# MCU.net
KiCad netlist of a schematic drawn in Altium Designer
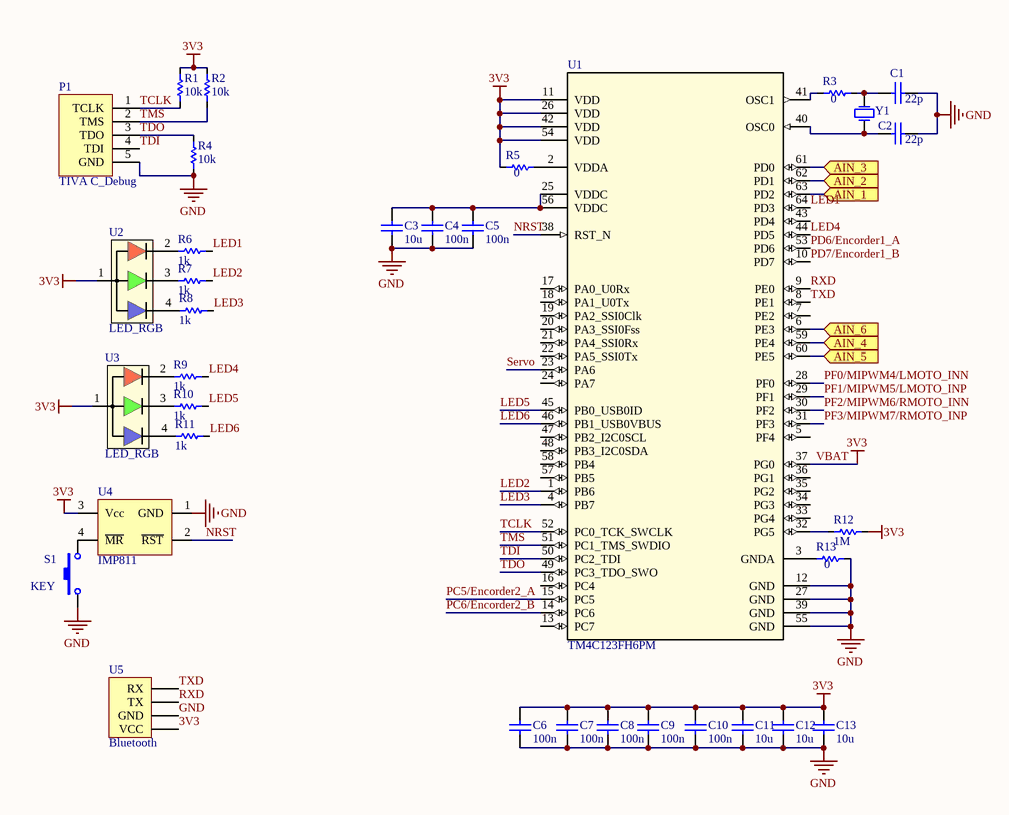
[diagram p0: MCU.SchDoc]

(export (version "E")
  (design (tool "Eeschema 10.0.6"))
  (components
    (comp (ref "C1")
      (value "22p")
      (footprint "0603C")
      (description "Capacitor")
      (fields (field (name "Comment") "1uF/0603/50V") (field (name "PUBLISHER") "Altium Limited"))
      (libsource (lib "OurSuperMiniCar") (part "Cap"))
    )
    (comp (ref "C2")
      (value "22p")
      (footprint "0603C")
      (description "Capacitor")
      (fields (field (name "Comment") "1uF/0603/50V") (field (name "PUBLISHER") "Altium Limited"))
      (libsource (lib "OurSuperMiniCar") (part "Cap"))
    )
    (comp (ref "C3")
      (value "10u")
      (footprint "0603C")
      (description "Capacitor")
      (fields (field (name "Comment") "1uF/0603/50V") (field (name "PUBLISHER") "Altium Limited"))
      (libsource (lib "OurSuperMiniCar") (part "Cap"))
    )
    (comp (ref "C4")
      (value "100n")
      (footprint "0603C")
      (description "Capacitor")
      (fields (field (name "Comment") "1uF/0603/50V") (field (name "PUBLISHER") "Altium Limited"))
      (libsource (lib "OurSuperMiniCar") (part "Cap"))
    )
    (comp (ref "C5")
      (value "100n")
      (footprint "0603C")
      (description "Capacitor")
      (fields (field (name "Comment") "1uF/0603/50V") (field (name "PUBLISHER") "Altium Limited"))
      (libsource (lib "OurSuperMiniCar") (part "Cap"))
    )
    (comp (ref "C6")
      (value "100n")
      (footprint "0603C")
      (description "Capacitor")
      (fields (field (name "Comment") "1uF/0603/50V") (field (name "PUBLISHER") "Altium Limited"))
      (libsource (lib "OurSuperMiniCar") (part "Cap"))
    )
    (comp (ref "C7")
      (value "100n")
      (footprint "0603C")
      (description "Capacitor")
      (fields (field (name "Comment") "1uF/0603/50V") (field (name "PUBLISHER") "Altium Limited"))
      (libsource (lib "OurSuperMiniCar") (part "Cap"))
    )
    (comp (ref "C8")
      (value "100n")
      (footprint "0603C")
      (description "Capacitor")
      (fields (field (name "Comment") "1uF/0603/50V") (field (name "PUBLISHER") "Altium Limited"))
      (libsource (lib "OurSuperMiniCar") (part "Cap"))
    )
    (comp (ref "C9")
      (value "100n")
      (footprint "0603C")
      (description "Capacitor")
      (fields (field (name "Comment") "1uF/0603/50V") (field (name "PUBLISHER") "Altium Limited"))
      (libsource (lib "OurSuperMiniCar") (part "Cap"))
    )
    (comp (ref "C10")
      (value "100n")
      (footprint "0603C")
      (description "Capacitor")
      (fields (field (name "Comment") "1uF/0603/50V") (field (name "PUBLISHER") "Altium Limited"))
      (libsource (lib "OurSuperMiniCar") (part "Cap"))
    )
    (comp (ref "C11")
      (value "10u")
      (footprint "0603C")
      (description "Capacitor")
      (fields (field (name "Comment") "1uF/0603/50V") (field (name "PUBLISHER") "Altium Limited"))
      (libsource (lib "OurSuperMiniCar") (part "Cap"))
    )
    (comp (ref "C12")
      (value "10u")
      (footprint "0603C")
      (description "Capacitor")
      (fields (field (name "Comment") "1uF/0603/50V") (field (name "PUBLISHER") "Altium Limited"))
      (libsource (lib "OurSuperMiniCar") (part "Cap"))
    )
    (comp (ref "C13")
      (value "10u")
      (footprint "0603C")
      (description "Capacitor")
      (fields (field (name "Comment") "1uF/0603/50V") (field (name "PUBLISHER") "Altium Limited"))
      (libsource (lib "OurSuperMiniCar") (part "Cap"))
    )
    (comp (ref "P1")
      (value "TIVA C_Debug")
      (footprint "SMT_HEADER5")
      (libsource (lib "OurSuperMiniCar") (part "TIVA C_Debug"))
    )
    (comp (ref "R1")
      (value "10k")
      (footprint "0603R")
      (description "Resistor")
      (fields (field (name "Comment") "1K/5%") (field (name "PUBLISHER") "Altium Limited"))
      (libsource (lib "OurSuperMiniCar") (part "Res1"))
    )
    (comp (ref "R2")
      (value "10k")
      (footprint "0603R")
      (description "Resistor")
      (fields (field (name "Comment") "1K/5%") (field (name "PUBLISHER") "Altium Limited"))
      (libsource (lib "OurSuperMiniCar") (part "Res1"))
    )
    (comp (ref "R3")
      (value "0")
      (footprint "0603R")
      (description "Resistor")
      (fields (field (name "Comment") "1K/5%") (field (name "PUBLISHER") "Altium Limited"))
      (libsource (lib "OurSuperMiniCar") (part "Res1"))
    )
    (comp (ref "R4")
      (value "10k")
      (footprint "0603R")
      (description "Resistor")
      (fields (field (name "Comment") "1K/5%") (field (name "PUBLISHER") "Altium Limited"))
      (libsource (lib "OurSuperMiniCar") (part "Res1"))
    )
    (comp (ref "R5")
      (value "0")
      (footprint "0603R")
      (description "Resistor")
      (fields (field (name "Comment") "1K/5%") (field (name "PUBLISHER") "Altium Limited"))
      (libsource (lib "OurSuperMiniCar") (part "Res1"))
    )
    (comp (ref "R6")
      (value "1k")
      (footprint "0402")
      (description "Resistor")
      (fields (field (name "Comment") "1K/5%") (field (name "PUBLISHER") "Altium Limited"))
      (libsource (lib "OurSuperMiniCar") (part "Res1"))
    )
    (comp (ref "R7")
      (value "1k")
      (footprint "0402")
      (description "Resistor")
      (fields (field (name "Comment") "1K/5%") (field (name "PUBLISHER") "Altium Limited"))
      (libsource (lib "OurSuperMiniCar") (part "Res1"))
    )
    (comp (ref "R8")
      (value "1k")
      (footprint "0402")
      (description "Resistor")
      (fields (field (name "Comment") "1K/5%") (field (name "PUBLISHER") "Altium Limited"))
      (libsource (lib "OurSuperMiniCar") (part "Res1"))
    )
    (comp (ref "R9")
      (value "1k")
      (footprint "0402")
      (description "Resistor")
      (fields (field (name "Comment") "1K/5%") (field (name "PUBLISHER") "Altium Limited"))
      (libsource (lib "OurSuperMiniCar") (part "Res1"))
    )
    (comp (ref "R10")
      (value "1k")
      (footprint "0402")
      (description "Resistor")
      (fields (field (name "Comment") "1K/5%") (field (name "PUBLISHER") "Altium Limited"))
      (libsource (lib "OurSuperMiniCar") (part "Res1"))
    )
    (comp (ref "R11")
      (value "1k")
      (footprint "0402")
      (description "Resistor")
      (fields (field (name "Comment") "1K/5%") (field (name "PUBLISHER") "Altium Limited"))
      (libsource (lib "OurSuperMiniCar") (part "Res1"))
    )
    (comp (ref "R12")
      (value "1M")
      (footprint "0603R")
      (description "Resistor")
      (fields (field (name "Comment") "1K/5%") (field (name "PUBLISHER") "Altium Limited"))
      (libsource (lib "OurSuperMiniCar") (part "Res1"))
    )
    (comp (ref "R13")
      (value "0")
      (footprint "0603R")
      (description "Resistor")
      (fields (field (name "Comment") "1K/5%") (field (name "PUBLISHER") "Altium Limited"))
      (libsource (lib "OurSuperMiniCar") (part "Res1"))
    )
    (comp (ref "S1")
      (value "KEY")
      (footprint "SW-3x6mm-SMT")
      (description "Button")
      (fields (field (name "PUBLISHER") "Altium Limited"))
      (libsource (lib "OurSuperMiniCar") (part "PushButton_2p"))
    )
    (comp (ref "U1")
      (value "TM4C123FH6PM")
      (footprint "LQFP_64")
      (libsource (lib "OurSuperMiniCar") (part "TM4C123FH6PM"))
    )
    (comp (ref "U2")
      (value "LED_RGB")
      (footprint "0603 RGB")
      (libsource (lib "OurSuperMiniCar") (part "LED_RGB"))
    )
    (comp (ref "U3")
      (value "LED_RGB")
      (footprint "0603 RGB")
      (libsource (lib "OurSuperMiniCar") (part "LED_RGB"))
    )
    (comp (ref "U4")
      (value "IMP811")
      (footprint "SOT143")
      (description "复位芯片")
      (libsource (lib "OurSuperMiniCar") (part "IMP811"))
    )
    (comp (ref "U5")
      (value "Bluetooth")
      (footprint "SMT_Female HEADER4")
      (description "Bluetooth Module")
      (libsource (lib "OurSuperMiniCar") (part "Bluetooth"))
    )
    (comp (ref "Y1")
      (value "XTAL")
      (footprint "NX5032GA")
      (description "Crystal Oscillator")
      (fields (field (name "PUBLISHER") "Altium Limited"))
      (libsource (lib "OurSuperMiniCar") (part "XTAL"))
    )
  )
  (nets
    (net (code "1") (name "/AIN_1") (class "Default")
      (node (ref "U1") (pin "63") (pinfunction "PD2_63") (pintype "bidirectional"))
    )
    (net (code "2") (name "/AIN_2") (class "Default")
      (node (ref "U1") (pin "62") (pinfunction "PD1_62") (pintype "bidirectional"))
    )
    (net (code "3") (name "/AIN_3") (class "Default")
      (node (ref "U1") (pin "61") (pinfunction "PD0_61") (pintype "bidirectional"))
    )
    (net (code "4") (name "/AIN_4") (class "Default")
      (node (ref "U1") (pin "59") (pinfunction "PE4_59") (pintype "bidirectional"))
    )
    (net (code "5") (name "/AIN_5") (class "Default")
      (node (ref "U1") (pin "60") (pinfunction "PE5_60") (pintype "bidirectional"))
    )
    (net (code "6") (name "/AIN_6") (class "Default")
      (node (ref "U1") (pin "6") (pinfunction "PE3_6") (pintype "bidirectional"))
    )
    (net (code "7") (name "/LED1") (class "Default")
      (node (ref "R6") (pin "2") (pinfunction "2_2") (pintype "passive"))
      (node (ref "U1") (pin "64") (pinfunction "PD3_64") (pintype "bidirectional"))
    )
    (net (code "8") (name "/LED2") (class "Default")
      (node (ref "R7") (pin "2") (pinfunction "2_2") (pintype "passive"))
      (node (ref "U1") (pin "1") (pinfunction "PB6_1") (pintype "bidirectional"))
    )
    (net (code "9") (name "/LED3") (class "Default")
      (node (ref "R8") (pin "2") (pinfunction "2_2") (pintype "passive"))
      (node (ref "U1") (pin "4") (pinfunction "PB7_4") (pintype "bidirectional"))
    )
    (net (code "10") (name "/LED4") (class "Default")
      (node (ref "R9") (pin "2") (pinfunction "2_2") (pintype "passive"))
      (node (ref "U1") (pin "44") (pinfunction "PD5_44") (pintype "bidirectional"))
    )
    (net (code "11") (name "/LED5") (class "Default")
      (node (ref "R10") (pin "2") (pinfunction "2_2") (pintype "passive"))
      (node (ref "U1") (pin "45") (pinfunction "PB0_USB0ID_45") (pintype "bidirectional"))
    )
    (net (code "12") (name "/LED6") (class "Default")
      (node (ref "R11") (pin "2") (pinfunction "2_2") (pintype "passive"))
      (node (ref "U1") (pin "46") (pinfunction "PB1_USB0VBUS_46") (pintype "bidirectional"))
    )
    (net (code "13") (name "/NRST") (class "Default")
      (node (ref "U1") (pin "38") (pinfunction "RST_N_38") (pintype "input"))
      (node (ref "U4") (pin "2") (pinfunction "~{RST}_2") (pintype "passive"))
    )
    (net (code "14") (name "/PC5{slash}Encorder2_A") (class "Default")
      (node (ref "U1") (pin "15") (pinfunction "PC5_15") (pintype "bidirectional"))
    )
    (net (code "15") (name "/PC6{slash}Encorder2_B") (class "Default")
      (node (ref "U1") (pin "14") (pinfunction "PC6_14") (pintype "bidirectional"))
    )
    (net (code "16") (name "/PD6{slash}Encorder1_A") (class "Default")
      (node (ref "U1") (pin "53") (pinfunction "PD6_53") (pintype "bidirectional"))
    )
    (net (code "17") (name "/PD7{slash}Encorder1_B") (class "Default")
      (node (ref "U1") (pin "10") (pinfunction "PD7_10") (pintype "bidirectional"))
    )
    (net (code "18") (name "/PF0{slash}MIPWM4{slash}LMOTO_INN") (class "Default")
      (node (ref "U1") (pin "28") (pinfunction "PF0_28") (pintype "bidirectional"))
    )
    (net (code "19") (name "/PF1{slash}MIPWM5{slash}LMOTO_INP") (class "Default")
      (node (ref "U1") (pin "29") (pinfunction "PF1_29") (pintype "bidirectional"))
    )
    (net (code "20") (name "/PF2{slash}MIPWM6{slash}RMOTO_INN") (class "Default")
      (node (ref "U1") (pin "30") (pinfunction "PF2_30") (pintype "bidirectional"))
    )
    (net (code "21") (name "/PF3{slash}MIPWM7{slash}RMOTO_INP") (class "Default")
      (node (ref "U1") (pin "31") (pinfunction "PF3_31") (pintype "bidirectional"))
    )
    (net (code "22") (name "/RXD") (class "Default")
      (node (ref "U1") (pin "9") (pinfunction "PE0_9") (pintype "bidirectional"))
      (node (ref "U5") (pin "2") (pinfunction "TX_2") (pintype "open_collector"))
    )
    (net (code "23") (name "/Servo") (class "Default")
      (node (ref "U1") (pin "23") (pinfunction "PA6_23") (pintype "bidirectional"))
    )
    (net (code "24") (name "/TCLK") (class "Default")
      (node (ref "P1") (pin "1") (pinfunction "TCLK_1") (pintype "passive"))
      (node (ref "R1") (pin "2") (pinfunction "2_2") (pintype "passive"))
      (node (ref "U1") (pin "52") (pinfunction "PC0_TCK_SWCLK_52") (pintype "bidirectional"))
    )
    (net (code "25") (name "/TDI") (class "Default")
      (node (ref "P1") (pin "4") (pinfunction "TDI_4") (pintype "passive"))
      (node (ref "U1") (pin "50") (pinfunction "PC2_TDI_50") (pintype "bidirectional"))
    )
    (net (code "26") (name "/TDO") (class "Default")
      (node (ref "P1") (pin "3") (pinfunction "TDO_3") (pintype "passive"))
      (node (ref "R4") (pin "1") (pinfunction "1_1") (pintype "passive"))
      (node (ref "U1") (pin "49") (pinfunction "PC3_TDO_SWO_49") (pintype "bidirectional"))
    )
    (net (code "27") (name "/TMS") (class "Default")
      (node (ref "P1") (pin "2") (pinfunction "TMS_2") (pintype "passive"))
      (node (ref "R2") (pin "2") (pinfunction "2_2") (pintype "passive"))
      (node (ref "U1") (pin "51") (pinfunction "PC1_TMS_SWDIO_51") (pintype "bidirectional"))
    )
    (net (code "28") (name "/TXD") (class "Default")
      (node (ref "U1") (pin "8") (pinfunction "PE1_8") (pintype "bidirectional"))
      (node (ref "U5") (pin "1") (pinfunction "RX_1") (pintype "open_collector"))
    )
    (net (code "29") (name "3V3") (class "Default")
      (node (ref "C10") (pin "2") (pinfunction "2_2") (pintype "passive"))
      (node (ref "C11") (pin "2") (pinfunction "2_2") (pintype "passive"))
      (node (ref "C12") (pin "2") (pinfunction "2_2") (pintype "passive"))
      (node (ref "C13") (pin "2") (pinfunction "2_2") (pintype "passive"))
      (node (ref "C6") (pin "2") (pinfunction "2_2") (pintype "passive"))
      (node (ref "C7") (pin "2") (pinfunction "2_2") (pintype "passive"))
      (node (ref "C8") (pin "2") (pinfunction "2_2") (pintype "passive"))
      (node (ref "C9") (pin "2") (pinfunction "2_2") (pintype "passive"))
      (node (ref "R1") (pin "1") (pinfunction "1_1") (pintype "passive"))
      (node (ref "R12") (pin "1") (pinfunction "1_1") (pintype "passive"))
      (node (ref "R2") (pin "1") (pinfunction "1_1") (pintype "passive"))
      (node (ref "R5") (pin "2") (pinfunction "2_2") (pintype "passive"))
      (node (ref "U1") (pin "11") (pinfunction "VDD_11") (pintype "power_in"))
      (node (ref "U1") (pin "26") (pinfunction "VDD_26") (pintype "power_in"))
      (node (ref "U1") (pin "37") (pinfunction "PG0_37") (pintype "bidirectional"))
      (node (ref "U1") (pin "42") (pinfunction "VDD_42") (pintype "power_in"))
      (node (ref "U1") (pin "54") (pinfunction "VDD_54") (pintype "power_in"))
      (node (ref "U2") (pin "1") (pinfunction "COM_1") (pintype "passive"))
      (node (ref "U3") (pin "1") (pinfunction "COM_1") (pintype "passive"))
      (node (ref "U4") (pin "3") (pinfunction "Vcc_3") (pintype "passive"))
      (node (ref "U5") (pin "4") (pinfunction "VCC_4") (pintype "open_collector"))
    )
    (net (code "30") (name "GND") (class "Default")
      (node (ref "C1") (pin "1") (pinfunction "1_1") (pintype "passive"))
      (node (ref "C10") (pin "1") (pinfunction "1_1") (pintype "passive"))
      (node (ref "C11") (pin "1") (pinfunction "1_1") (pintype "passive"))
      (node (ref "C12") (pin "1") (pinfunction "1_1") (pintype "passive"))
      (node (ref "C13") (pin "1") (pinfunction "1_1") (pintype "passive"))
      (node (ref "C2") (pin "1") (pinfunction "1_1") (pintype "passive"))
      (node (ref "C3") (pin "1") (pinfunction "1_1") (pintype "passive"))
      (node (ref "C4") (pin "1") (pinfunction "1_1") (pintype "passive"))
      (node (ref "C5") (pin "1") (pinfunction "1_1") (pintype "passive"))
      (node (ref "C6") (pin "1") (pinfunction "1_1") (pintype "passive"))
      (node (ref "C7") (pin "1") (pinfunction "1_1") (pintype "passive"))
      (node (ref "C8") (pin "1") (pinfunction "1_1") (pintype "passive"))
      (node (ref "C9") (pin "1") (pinfunction "1_1") (pintype "passive"))
      (node (ref "P1") (pin "5") (pinfunction "GND_5") (pintype "passive"))
      (node (ref "R13") (pin "1") (pinfunction "1_1") (pintype "passive"))
      (node (ref "R4") (pin "2") (pinfunction "2_2") (pintype "passive"))
      (node (ref "S1") (pin "2") (pinfunction "2_2") (pintype "passive"))
      (node (ref "U1") (pin "12") (pinfunction "GND_12") (pintype "power_in"))
      (node (ref "U1") (pin "27") (pinfunction "GND_27") (pintype "power_in"))
      (node (ref "U1") (pin "39") (pinfunction "GND_39") (pintype "power_in"))
      (node (ref "U1") (pin "55") (pinfunction "GND_55") (pintype "power_in"))
      (node (ref "U4") (pin "1") (pinfunction "GND_1") (pintype "passive"))
      (node (ref "U5") (pin "3") (pinfunction "GND_3") (pintype "open_collector"))
    )
    (net (code "31") (name "Net-(C3-Pad2)") (class "Default")
      (node (ref "C3") (pin "2") (pinfunction "2_2") (pintype "passive"))
      (node (ref "C4") (pin "2") (pinfunction "2_2") (pintype "passive"))
      (node (ref "C5") (pin "2") (pinfunction "2_2") (pintype "passive"))
      (node (ref "U1") (pin "25") (pinfunction "VDDC_25") (pintype "power_in"))
      (node (ref "U1") (pin "56") (pinfunction "VDDC_56") (pintype "power_in"))
    )
    (net (code "32") (name "Net-(R6-Pad1)") (class "Default")
      (node (ref "R6") (pin "1") (pinfunction "1_1") (pintype "passive"))
      (node (ref "U2") (pin "2") (pinfunction "2_2") (pintype "open_collector"))
    )
    (net (code "33") (name "Net-(R7-Pad1)") (class "Default")
      (node (ref "R7") (pin "1") (pinfunction "1_1") (pintype "passive"))
      (node (ref "U2") (pin "3") (pinfunction "3_3") (pintype "open_collector"))
    )
    (net (code "34") (name "Net-(R8-Pad1)") (class "Default")
      (node (ref "R8") (pin "1") (pinfunction "1_1") (pintype "passive"))
      (node (ref "U2") (pin "4") (pinfunction "4_4") (pintype "open_collector"))
    )
    (net (code "35") (name "Net-(R9-Pad1)") (class "Default")
      (node (ref "R9") (pin "1") (pinfunction "1_1") (pintype "passive"))
      (node (ref "U3") (pin "2") (pinfunction "2_2") (pintype "open_collector"))
    )
    (net (code "36") (name "Net-(R10-Pad1)") (class "Default")
      (node (ref "R10") (pin "1") (pinfunction "1_1") (pintype "passive"))
      (node (ref "U3") (pin "3") (pinfunction "3_3") (pintype "open_collector"))
    )
    (net (code "37") (name "Net-(R11-Pad1)") (class "Default")
      (node (ref "R11") (pin "1") (pinfunction "1_1") (pintype "passive"))
      (node (ref "U3") (pin "4") (pinfunction "4_4") (pintype "open_collector"))
    )
    (net (code "38") (name "Net-(U1-GNDA)") (class "Default")
      (node (ref "R13") (pin "2") (pinfunction "2_2") (pintype "passive"))
      (node (ref "U1") (pin "3") (pinfunction "GNDA_3") (pintype "power_in"))
    )
    (net (code "39") (name "Net-(U1-OSC0)") (class "Default")
      (node (ref "C2") (pin "2") (pinfunction "2_2") (pintype "passive"))
      (node (ref "U1") (pin "40") (pinfunction "OSC0_40") (pintype "input"))
      (node (ref "Y1") (pin "1") (pinfunction "OSC1_1") (pintype "passive"))
    )
    (net (code "40") (name "Net-(U1-OSC1)") (class "Default")
      (node (ref "R3") (pin "2") (pinfunction "2_2") (pintype "passive"))
      (node (ref "U1") (pin "41") (pinfunction "OSC1_41") (pintype "output"))
    )
    (net (code "41") (name "Net-(U1-PG5)") (class "Default")
      (node (ref "R12") (pin "2") (pinfunction "2_2") (pintype "passive"))
      (node (ref "U1") (pin "32") (pinfunction "PG5_32") (pintype "bidirectional"))
    )
    (net (code "42") (name "Net-(U1-VDDA)") (class "Default")
      (node (ref "R5") (pin "1") (pinfunction "1_1") (pintype "passive"))
      (node (ref "U1") (pin "2") (pinfunction "VDDA_2") (pintype "power_in"))
    )
    (net (code "43") (name "Net-(U4-~{MR})") (class "Default")
      (node (ref "S1") (pin "1") (pinfunction "1_1") (pintype "passive"))
      (node (ref "U4") (pin "4") (pinfunction "~{MR}_4") (pintype "passive"))
    )
    (net (code "44") (name "Net-(Y1-OSC2)") (class "Default")
      (node (ref "C1") (pin "2") (pinfunction "2_2") (pintype "passive"))
      (node (ref "R3") (pin "1") (pinfunction "1_1") (pintype "passive"))
      (node (ref "Y1") (pin "2") (pinfunction "OSC2_2") (pintype "passive"))
    )
    (net (code "45") (name "unconnected-(U1-PA0_U0Rx-Pad17)") (class "Default")
      (node (ref "U1") (pin "17") (pinfunction "PA0_U0Rx_17") (pintype "bidirectional"))
    )
    (net (code "46") (name "unconnected-(U1-PA1_U0Tx-Pad18)") (class "Default")
      (node (ref "U1") (pin "18") (pinfunction "PA1_U0Tx_18") (pintype "bidirectional"))
    )
    (net (code "47") (name "unconnected-(U1-PA2_SSI0Clk-Pad19)") (class "Default")
      (node (ref "U1") (pin "19") (pinfunction "PA2_SSI0Clk_19") (pintype "bidirectional"))
    )
    (net (code "48") (name "unconnected-(U1-PA3_SSI0Fss-Pad20)") (class "Default")
      (node (ref "U1") (pin "20") (pinfunction "PA3_SSI0Fss_20") (pintype "bidirectional"))
    )
    (net (code "49") (name "unconnected-(U1-PA4_SSI0Rx-Pad21)") (class "Default")
      (node (ref "U1") (pin "21") (pinfunction "PA4_SSI0Rx_21") (pintype "bidirectional"))
    )
    (net (code "50") (name "unconnected-(U1-PA5_SSI0Tx-Pad22)") (class "Default")
      (node (ref "U1") (pin "22") (pinfunction "PA5_SSI0Tx_22") (pintype "bidirectional"))
    )
    (net (code "51") (name "unconnected-(U1-PA7-Pad24)") (class "Default")
      (node (ref "U1") (pin "24") (pinfunction "PA7_24") (pintype "bidirectional"))
    )
    (net (code "52") (name "unconnected-(U1-PB2_I2C0SCL-Pad47)") (class "Default")
      (node (ref "U1") (pin "47") (pinfunction "PB2_I2C0SCL_47") (pintype "bidirectional"))
    )
    (net (code "53") (name "unconnected-(U1-PB3_I2C0SDA-Pad48)") (class "Default")
      (node (ref "U1") (pin "48") (pinfunction "PB3_I2C0SDA_48") (pintype "bidirectional"))
    )
    (net (code "54") (name "unconnected-(U1-PB4-Pad58)") (class "Default")
      (node (ref "U1") (pin "58") (pinfunction "PB4_58") (pintype "bidirectional"))
    )
    (net (code "55") (name "unconnected-(U1-PB5-Pad57)") (class "Default")
      (node (ref "U1") (pin "57") (pinfunction "PB5_57") (pintype "bidirectional"))
    )
    (net (code "56") (name "unconnected-(U1-PC4-Pad16)") (class "Default")
      (node (ref "U1") (pin "16") (pinfunction "PC4_16") (pintype "bidirectional"))
    )
    (net (code "57") (name "unconnected-(U1-PC7-Pad13)") (class "Default")
      (node (ref "U1") (pin "13") (pinfunction "PC7_13") (pintype "bidirectional"))
    )
    (net (code "58") (name "unconnected-(U1-PD4-Pad43)") (class "Default")
      (node (ref "U1") (pin "43") (pinfunction "PD4_43") (pintype "bidirectional"))
    )
    (net (code "59") (name "unconnected-(U1-PE2-Pad7)") (class "Default")
      (node (ref "U1") (pin "7") (pinfunction "PE2_7") (pintype "bidirectional"))
    )
    (net (code "60") (name "unconnected-(U1-PF4-Pad5)") (class "Default")
      (node (ref "U1") (pin "5") (pinfunction "PF4_5") (pintype "bidirectional"))
    )
    (net (code "61") (name "unconnected-(U1-PG1-Pad36)") (class "Default")
      (node (ref "U1") (pin "36") (pinfunction "PG1_36") (pintype "bidirectional"))
    )
    (net (code "62") (name "unconnected-(U1-PG2-Pad35)") (class "Default")
      (node (ref "U1") (pin "35") (pinfunction "PG2_35") (pintype "bidirectional"))
    )
    (net (code "63") (name "unconnected-(U1-PG3-Pad34)") (class "Default")
      (node (ref "U1") (pin "34") (pinfunction "PG3_34") (pintype "bidirectional"))
    )
    (net (code "64") (name "unconnected-(U1-PG4-Pad33)") (class "Default")
      (node (ref "U1") (pin "33") (pinfunction "PG4_33") (pintype "bidirectional"))
    )
  )
)
